# Power_Board.net
KiCad netlist of a schematic drawn in EAGLE
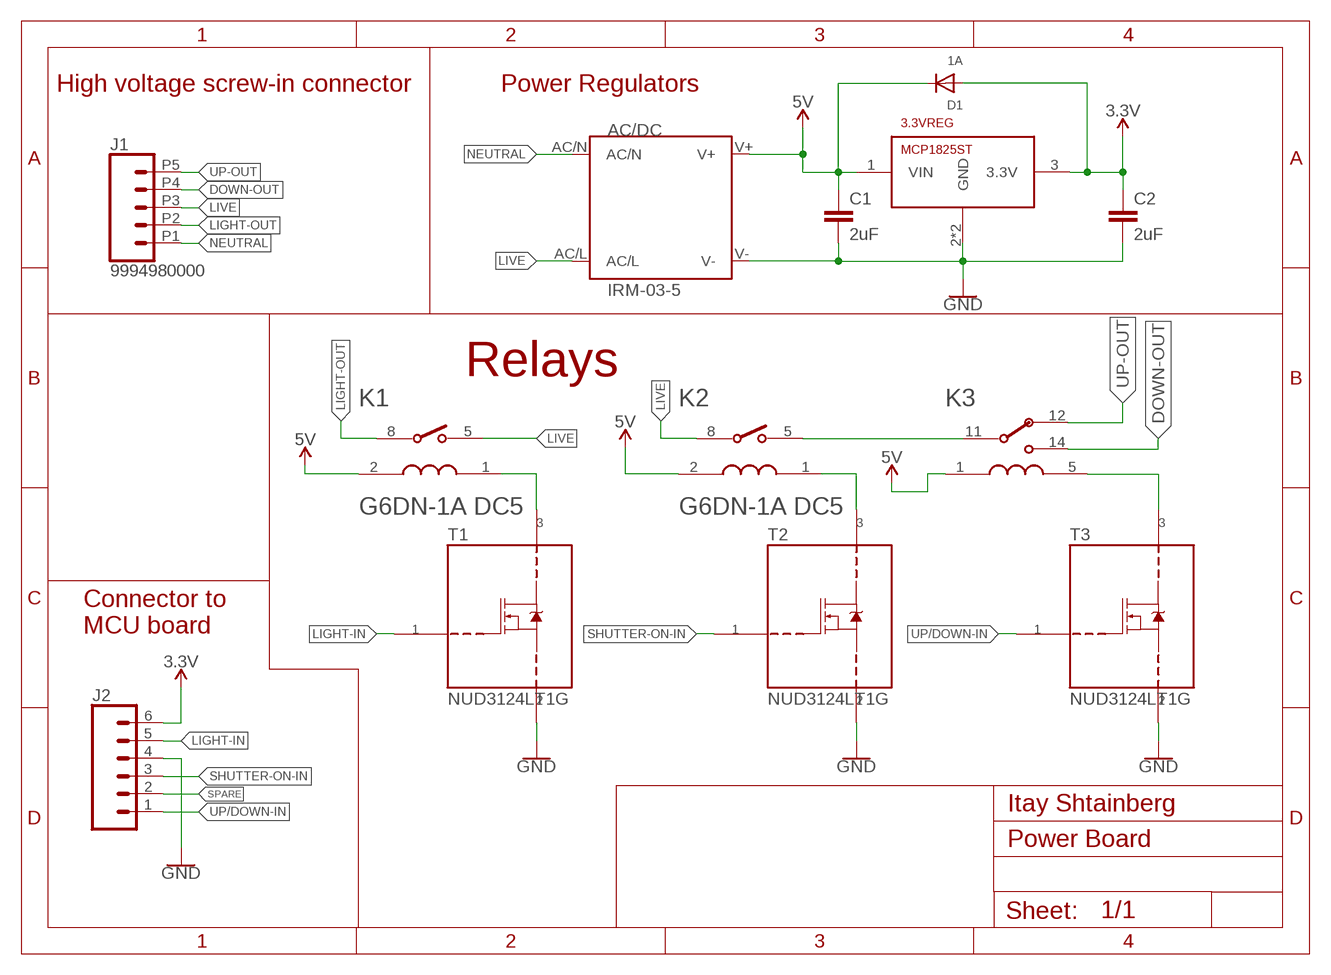
[diagram p0: schematic, sheet 1]

(export (version "E")
  (design (tool "Eeschema 10.0.6"))
  (components
    (comp (ref "3.3VREG")
      (value "MCP1825ST")
      (footprint "eagle-import:SOT223")
      (libsource (lib "eagle-import") (part "MCP1825ST-3302E/DB"))
    )
    (comp (ref "AC/DC")
      (value "IRM-03-5")
      (footprint "eagle-import:IRM_03")
      (libsource (lib "eagle-import") (part "IRM_03IRM_03"))
    )
    (comp (ref "C1")
      (value "2uF")
      (footprint "eagle-import:C0805")
      (libsource (lib "eagle-import") (part "C"))
    )
    (comp (ref "C2")
      (value "2uF")
      (footprint "eagle-import:C0805")
      (libsource (lib "eagle-import") (part "C"))
    )
    (comp (ref "D1")
      (value "1A")
      (footprint "eagle-import:SOD-123")
      (libsource (lib "eagle-import") (part "DIODESOD-123"))
    )
    (comp (ref "J1")
      (value "9994980000")
      (footprint "eagle-import:9994980000")
      (libsource (lib "eagle-import") (part "9994980000"))
    )
    (comp (ref "J2")
      (value "CONN_06FEMALE_LOCK")
      (footprint "eagle-import:1X06_FEMALE_LOCK.010")
      (libsource (lib "eagle-import") (part "CONN_06FEMALE_LOCK"))
    )
    (comp (ref "K1")
      (value "G6DN-1A-L DC5")
      (footprint "eagle-import:OMRON_G6DN-1A_DC5_0")
      (fields
        (field (name "DIGIKEY_PART_NUMBER") "Z5439-N")
        (field (name "MF") "Omron")
        (field (name "MOUSER_PART_NUMBER") "653-G6DN1ADC5")
      )
      (libsource (lib "eagle-import") (part "OMRON_G6DN-1A_DC5OMRON_G6DN-1A_DC5_0_0"))
    )
    (comp (ref "K2")
      (value "G6DN-1A-L DC5")
      (footprint "eagle-import:OMRON_G6DN-1A_DC5_0")
      (fields
        (field (name "DIGIKEY_PART_NUMBER") "Z5439-N")
        (field (name "MF") "Omron")
        (field (name "MOUSER_PART_NUMBER") "653-G6DN1ADC5")
      )
      (libsource (lib "eagle-import") (part "OMRON_G6DN-1A_DC5OMRON_G6DN-1A_DC5_0_0"))
    )
    (comp (ref "K3")
      (value "PE014005")
      (footprint "eagle-import:RELAY5-PE_CO")
      (fields (field (name "COPYRIGHT") "Copyright (C) 2016 Accelerated Designs. All rights reserved"))
      (libsource (lib "eagle-import") (part "PE014005"))
    )
    (comp (ref "T1")
      (value "NUD3124LT1G")
      (footprint "eagle-import:SOT23")
      (libsource (lib "eagle-import") (part "NUD3124LT1G"))
    )
    (comp (ref "T2")
      (value "NUD3124LT1G")
      (footprint "eagle-import:SOT23")
      (libsource (lib "eagle-import") (part "NUD3124LT1G"))
    )
    (comp (ref "T3")
      (value "NUD3124LT1G")
      (footprint "eagle-import:SOT23")
      (libsource (lib "eagle-import") (part "NUD3124LT1G"))
    )
  )
  (nets
    (net (code "1") (name "3.3V") (class "Default")
      (node (ref "3.3VREG") (pin "3") (pinfunction "3.3V_3") (pintype "power_in"))
      (node (ref "C2") (pin "1") (pinfunction "1_1") (pintype "passive"))
      (node (ref "D1") (pin "A") (pinfunction "A_A") (pintype "passive"))
      (node (ref "J2") (pin "6") (pinfunction "6_6") (pintype "passive"))
    )
    (net (code "2") (name "5V") (class "Default")
      (node (ref "3.3VREG") (pin "1") (pinfunction "VIN_1") (pintype "power_in"))
      (node (ref "AC/DC") (pin "V+") (pinfunction "V+_V+") (pintype "output"))
      (node (ref "C1") (pin "1") (pinfunction "1_1") (pintype "passive"))
      (node (ref "D1") (pin "C") (pinfunction "C_C") (pintype "passive"))
      (node (ref "K1") (pin "2") (pinfunction "2_2") (pintype "bidirectional"))
      (node (ref "K2") (pin "2") (pinfunction "2_2") (pintype "bidirectional"))
      (node (ref "K3") (pin "1") (pinfunction "COIL1_1") (pintype "bidirectional"))
    )
    (net (code "3") (name "DOWN-OUT") (class "Default")
      (node (ref "J1") (pin "P4") (pinfunction "4_P4") (pintype "passive"))
      (node (ref "K3") (pin "14") (pinfunction "NO_14") (pintype "bidirectional"))
    )
    (net (code "4") (name "GND") (class "Default")
      (node (ref "3.3VREG") (pin "2") (pinfunction "GND_2") (pintype "power_in"))
      (node (ref "3.3VREG") (pin "4") (pinfunction "GND_4") (pintype "power_in"))
      (node (ref "AC/DC") (pin "V-") (pinfunction "V-_V-") (pintype "output"))
      (node (ref "C1") (pin "2") (pinfunction "2_2") (pintype "passive"))
      (node (ref "C2") (pin "2") (pinfunction "2_2") (pintype "passive"))
      (node (ref "J2") (pin "4") (pinfunction "4_4") (pintype "passive"))
      (node (ref "T1") (pin "2") (pinfunction "P$2_2") (pintype "bidirectional"))
      (node (ref "T2") (pin "2") (pinfunction "P$2_2") (pintype "bidirectional"))
      (node (ref "T3") (pin "2") (pinfunction "P$2_2") (pintype "bidirectional"))
    )
    (net (code "5") (name "LIGHT-IN") (class "Default")
      (node (ref "J2") (pin "5") (pinfunction "5_5") (pintype "passive"))
      (node (ref "T1") (pin "1") (pinfunction "P$1_1") (pintype "bidirectional"))
    )
    (net (code "6") (name "LIGHT-OUT") (class "Default")
      (node (ref "J1") (pin "P2") (pinfunction "2_P2") (pintype "passive"))
      (node (ref "K1") (pin "8") (pinfunction "8_8") (pintype "bidirectional"))
    )
    (net (code "7") (name "LIVE") (class "Default")
      (node (ref "AC/DC") (pin "AC/L") (pinfunction "AC/L_AC/L") (pintype "input"))
      (node (ref "J1") (pin "P3") (pinfunction "3_P3") (pintype "passive"))
      (node (ref "K1") (pin "5") (pinfunction "5_5") (pintype "bidirectional"))
      (node (ref "K2") (pin "8") (pinfunction "8_8") (pintype "bidirectional"))
    )
    (net (code "8") (name "NEUTRAL") (class "Default")
      (node (ref "AC/DC") (pin "AC/N") (pinfunction "AC/N_AC/N") (pintype "input"))
      (node (ref "J1") (pin "P1") (pinfunction "1_P1") (pintype "passive"))
    )
    (net (code "9") (name "Net-(K3-COIL2)") (class "Default")
      (node (ref "K3") (pin "5") (pinfunction "COIL2_5") (pintype "bidirectional"))
      (node (ref "T3") (pin "3") (pinfunction "P$3_3") (pintype "bidirectional"))
    )
    (net (code "10") (name "Net-(K3-P)") (class "Default")
      (node (ref "K2") (pin "5") (pinfunction "5_5") (pintype "bidirectional"))
      (node (ref "K3") (pin "11") (pinfunction "P_11") (pintype "bidirectional"))
    )
    (net (code "11") (name "Net-(T1-P$3)") (class "Default")
      (node (ref "K1") (pin "1") (pinfunction "1_1") (pintype "bidirectional"))
      (node (ref "T1") (pin "3") (pinfunction "P$3_3") (pintype "bidirectional"))
    )
    (net (code "12") (name "Net-(T2-P$3)") (class "Default")
      (node (ref "K2") (pin "1") (pinfunction "1_1") (pintype "bidirectional"))
      (node (ref "T2") (pin "3") (pinfunction "P$3_3") (pintype "bidirectional"))
    )
    (net (code "13") (name "SHUTTER-ON-IN") (class "Default")
      (node (ref "J2") (pin "3") (pinfunction "3_3") (pintype "passive"))
      (node (ref "T2") (pin "1") (pinfunction "P$1_1") (pintype "bidirectional"))
    )
    (net (code "14") (name "SPARE") (class "Default")
      (node (ref "J2") (pin "2") (pinfunction "2_2") (pintype "passive"))
    )
    (net (code "15") (name "UP-OUT") (class "Default")
      (node (ref "J1") (pin "P5") (pinfunction "5_P5") (pintype "passive"))
      (node (ref "K3") (pin "12") (pinfunction "NC_12") (pintype "bidirectional"))
    )
    (net (code "16") (name "UP{slash}DOWN-IN") (class "Default")
      (node (ref "J2") (pin "1") (pinfunction "1_1") (pintype "passive"))
      (node (ref "T3") (pin "1") (pinfunction "P$1_1") (pintype "bidirectional"))
    )
  )
)
